# HARE_Main_Sch_Rev1.net
KiCad netlist of a schematic drawn in EAGLE
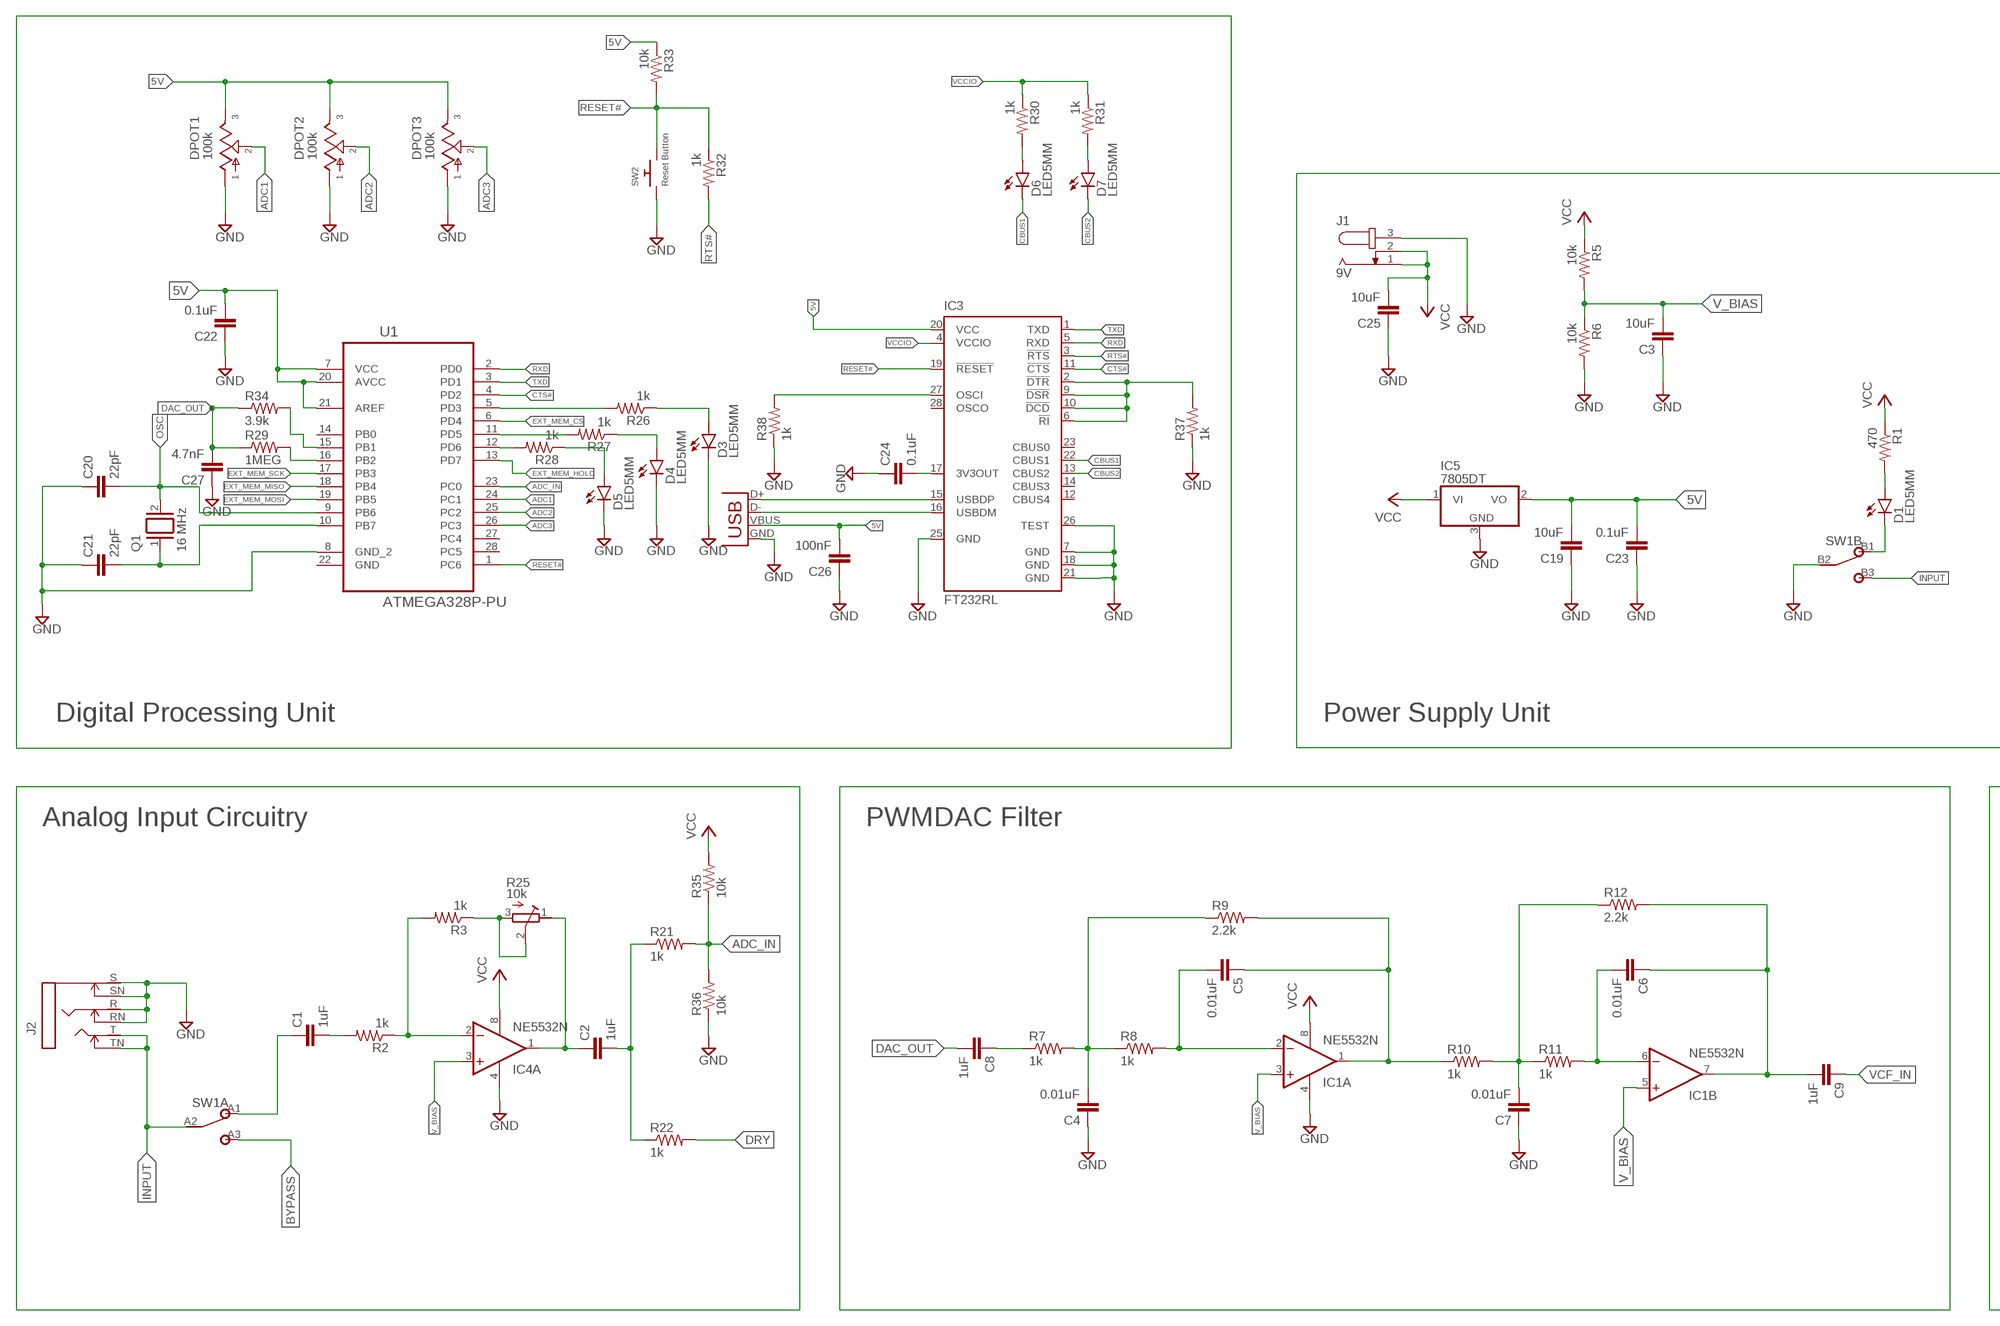
[diagram p0: schematic, sheet 1, part 1 of 2]
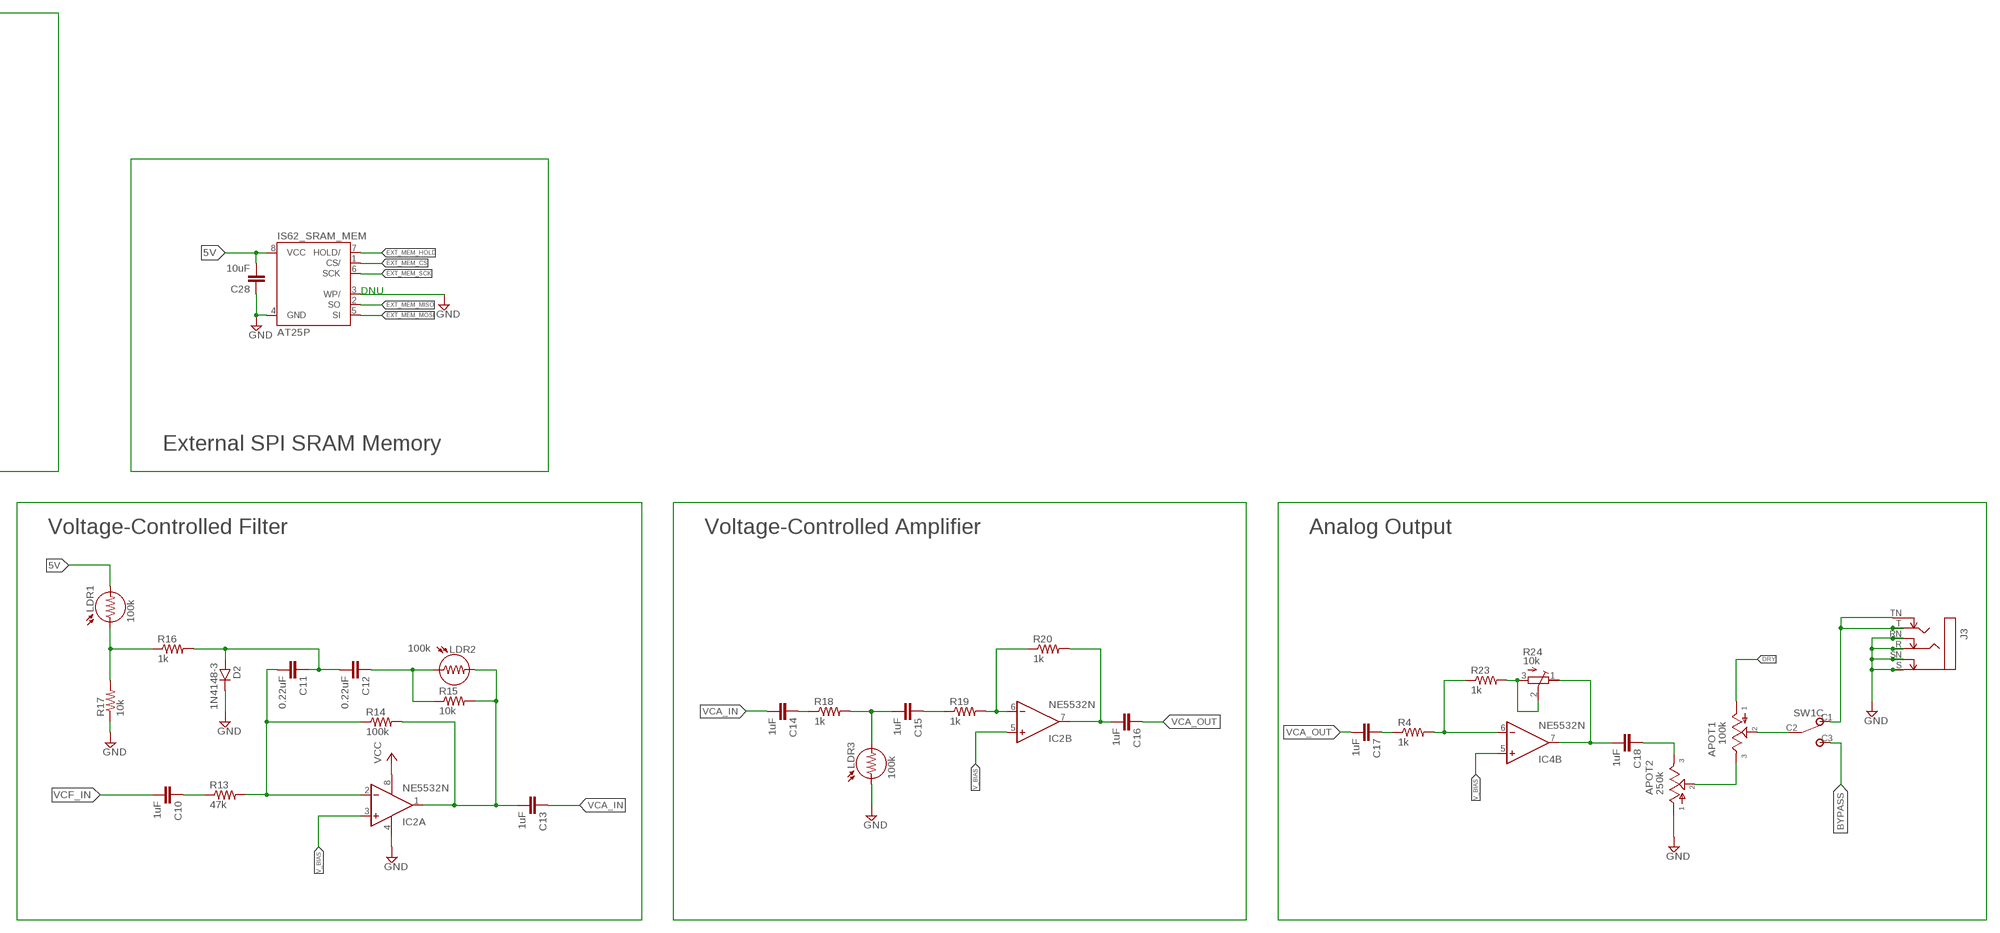
[diagram p1: schematic, sheet 1, part 2 of 2]

(export (version "E")
  (design (tool "Eeschema 10.0.6"))
  (components
    (comp (ref "APOT1")
      (value "100k")
      (footprint "eagle-import:16MM-SQUARE")
      (libsource (lib "eagle-import") (part "POTS"))
    )
    (comp (ref "APOT2")
      (value "250k")
      (footprint "eagle-import:16MM-SQUARE")
      (libsource (lib "eagle-import") (part "POTS"))
    )
    (comp (ref "C1")
      (value "1uF")
      (footprint "eagle-import:C0805K")
      (libsource (lib "eagle-import") (part "C-EUC0805K"))
    )
    (comp (ref "C2")
      (value "1uF")
      (footprint "eagle-import:C0805K")
      (libsource (lib "eagle-import") (part "C-EUC0805K"))
    )
    (comp (ref "C3")
      (value "10uF")
      (footprint "eagle-import:C0805K")
      (libsource (lib "eagle-import") (part "C-EUC0805K"))
    )
    (comp (ref "C4")
      (value "0.01uF")
      (footprint "eagle-import:C0805K")
      (libsource (lib "eagle-import") (part "C-EUC0805K"))
    )
    (comp (ref "C5")
      (value "0.01uF")
      (footprint "eagle-import:C0805K")
      (libsource (lib "eagle-import") (part "C-EUC0805K"))
    )
    (comp (ref "C6")
      (value "0.01uF")
      (footprint "eagle-import:C0805K")
      (libsource (lib "eagle-import") (part "C-EUC0805K"))
    )
    (comp (ref "C7")
      (value "0.01uF")
      (footprint "eagle-import:C0805K")
      (libsource (lib "eagle-import") (part "C-EUC0805K"))
    )
    (comp (ref "C8")
      (value "1uF")
      (footprint "eagle-import:C0805K")
      (libsource (lib "eagle-import") (part "C-EUC0805K"))
    )
    (comp (ref "C9")
      (value "1uF")
      (footprint "eagle-import:C0805K")
      (libsource (lib "eagle-import") (part "C-EUC0805K"))
    )
    (comp (ref "C10")
      (value "1uF")
      (footprint "eagle-import:C0805K")
      (libsource (lib "eagle-import") (part "C-EUC0805K"))
    )
    (comp (ref "C11")
      (value "0.22uF")
      (footprint "eagle-import:C0805K")
      (libsource (lib "eagle-import") (part "C-EUC0805K"))
    )
    (comp (ref "C12")
      (value "0.22uF")
      (footprint "eagle-import:C0805K")
      (libsource (lib "eagle-import") (part "C-EUC0805K"))
    )
    (comp (ref "C13")
      (value "1uF")
      (footprint "eagle-import:C0805K")
      (libsource (lib "eagle-import") (part "C-EUC0805K"))
    )
    (comp (ref "C14")
      (value "1uF")
      (footprint "eagle-import:C0805K")
      (libsource (lib "eagle-import") (part "C-EUC0805K"))
    )
    (comp (ref "C15")
      (value "1uF")
      (footprint "eagle-import:C0805K")
      (libsource (lib "eagle-import") (part "C-EUC0805K"))
    )
    (comp (ref "C16")
      (value "1uF")
      (footprint "eagle-import:C0805K")
      (libsource (lib "eagle-import") (part "C-EUC0805K"))
    )
    (comp (ref "C17")
      (value "1uF")
      (footprint "eagle-import:C0805K")
      (libsource (lib "eagle-import") (part "C-EUC0805K"))
    )
    (comp (ref "C18")
      (value "1uF")
      (footprint "eagle-import:C0805K")
      (libsource (lib "eagle-import") (part "C-EUC0805K"))
    )
    (comp (ref "C19")
      (value "10uF")
      (footprint "eagle-import:C0805K")
      (libsource (lib "eagle-import") (part "C-EUC0805K"))
    )
    (comp (ref "C20")
      (value "22pF")
      (footprint "eagle-import:C0805K")
      (libsource (lib "eagle-import") (part "C-EUC0805K"))
    )
    (comp (ref "C21")
      (value "22pF")
      (footprint "eagle-import:C0805K")
      (libsource (lib "eagle-import") (part "C-EUC0805K"))
    )
    (comp (ref "C22")
      (value "0.1uF")
      (footprint "eagle-import:C0805K")
      (libsource (lib "eagle-import") (part "C-EUC0805K"))
    )
    (comp (ref "C23")
      (value "0.1uF")
      (footprint "eagle-import:C0805K")
      (libsource (lib "eagle-import") (part "C-EUC0805K"))
    )
    (comp (ref "C24")
      (value "0.1uF")
      (footprint "eagle-import:C0805K")
      (libsource (lib "eagle-import") (part "C-EUC0805K"))
    )
    (comp (ref "C25")
      (value "10uF")
      (footprint "eagle-import:C0805K")
      (libsource (lib "eagle-import") (part "C-EUC0805K"))
    )
    (comp (ref "C26")
      (value "100nF")
      (footprint "eagle-import:C0805K")
      (libsource (lib "eagle-import") (part "C-EUC0805K"))
    )
    (comp (ref "C27")
      (value "4.7nF")
      (footprint "eagle-import:C0805K")
      (libsource (lib "eagle-import") (part "C-EUC0805K"))
    )
    (comp (ref "C28")
      (value "10uF")
      (footprint "eagle-import:C0805K")
      (libsource (lib "eagle-import") (part "C-EUC0805K"))
    )
    (comp (ref "D1")
      (value "LED5MM")
      (footprint "eagle-import:LED5MM")
      (libsource (lib "eagle-import") (part "LED5MM"))
    )
    (comp (ref "D2")
      (value "1N4148-3")
      (footprint "eagle-import:DO35-3")
      (libsource (lib "eagle-import") (part "1N4148-3"))
    )
    (comp (ref "D3")
      (value "LED5MM")
      (footprint "eagle-import:LED5MM")
      (libsource (lib "eagle-import") (part "LED5MM"))
    )
    (comp (ref "D4")
      (value "LED5MM")
      (footprint "eagle-import:LED5MM")
      (libsource (lib "eagle-import") (part "LED5MM"))
    )
    (comp (ref "D5")
      (value "LED5MM")
      (footprint "eagle-import:LED5MM")
      (libsource (lib "eagle-import") (part "LED5MM"))
    )
    (comp (ref "D6")
      (value "LED5MM")
      (footprint "eagle-import:LED5MM")
      (libsource (lib "eagle-import") (part "LED5MM"))
    )
    (comp (ref "D7")
      (value "LED5MM")
      (footprint "eagle-import:LED5MM")
      (libsource (lib "eagle-import") (part "LED5MM"))
    )
    (comp (ref "DPOT1")
      (value "100k")
      (footprint "eagle-import:16MM-SQUARE")
      (libsource (lib "eagle-import") (part "POTS"))
    )
    (comp (ref "DPOT2")
      (value "100k")
      (footprint "eagle-import:16MM-SQUARE")
      (libsource (lib "eagle-import") (part "POTS"))
    )
    (comp (ref "DPOT3")
      (value "100k")
      (footprint "eagle-import:16MM-SQUARE")
      (libsource (lib "eagle-import") (part "POTS"))
    )
    (comp (ref "IC1")
      (value "NE5532N")
      (footprint "eagle-import:DIL08")
      (libsource (lib "eagle-import") (part "NE5532N"))
    )
    (comp (ref "IC2")
      (value "NE5532N")
      (footprint "eagle-import:DIL08")
      (libsource (lib "eagle-import") (part "NE5532N"))
    )
    (comp (ref "IC3")
      (value "FT232RL")
      (footprint "eagle-import:SSOP28")
      (libsource (lib "eagle-import") (part "FT232RL"))
    )
    (comp (ref "IC4")
      (value "NE5532N")
      (footprint "eagle-import:DIL08")
      (libsource (lib "eagle-import") (part "NE5532N"))
    )
    (comp (ref "IC5")
      (value "7805DT")
      (footprint "eagle-import:TO252")
      (libsource (lib "eagle-import") (part "78DT05"))
    )
    (comp (ref "IS62_SRAM_MEM")
      (value "AT25P")
      (footprint "eagle-import:DIL08")
      (fields (field (name "MPN") "CAT25040LI-G"))
      (libsource (lib "eagle-import") (part "AT25P"))
    )
    (comp (ref "J1")
      (value "9V")
      (footprint "eagle-import:SPC4078")
      (libsource (lib "eagle-import") (part "JACK-PLUG1"))
    )
    (comp (ref "J2")
      (value "STEREOSW")
      (footprint "eagle-import:NMJ6HCD2")
      (libsource (lib "eagle-import") (part "STEREOSW"))
    )
    (comp (ref "J3")
      (value "STEREOSW")
      (footprint "eagle-import:NMJ6HCD2")
      (libsource (lib "eagle-import") (part "STEREOSW"))
    )
    (comp (ref "LDR1")
      (value "100k")
      (footprint "eagle-import:LDR338-54C")
      (libsource (lib "eagle-import") (part "LDR5MM"))
    )
    (comp (ref "LDR2")
      (value "100k")
      (footprint "eagle-import:LDR338-54C")
      (libsource (lib "eagle-import") (part "LDR5MM"))
    )
    (comp (ref "LDR3")
      (value "100k")
      (footprint "eagle-import:LDR338-54C")
      (libsource (lib "eagle-import") (part "LDR5MM"))
    )
    (comp (ref "Q1")
      (value "16 MHz")
      (footprint "eagle-import:QS")
      (libsource (lib "eagle-import") (part "XTAL/S"))
    )
    (comp (ref "R1")
      (value "470")
      (footprint "eagle-import:M0805")
      (libsource (lib "eagle-import") (part "R-US_M0805"))
    )
    (comp (ref "R2")
      (value "1k")
      (footprint "eagle-import:R0805")
      (libsource (lib "eagle-import") (part "resistor_R-US_R0805"))
    )
    (comp (ref "R3")
      (value "1k")
      (footprint "eagle-import:R0805")
      (libsource (lib "eagle-import") (part "resistor_R-US_R0805"))
    )
    (comp (ref "R4")
      (value "1k")
      (footprint "eagle-import:R0805")
      (libsource (lib "eagle-import") (part "resistor_R-US_R0805"))
    )
    (comp (ref "R5")
      (value "10k")
      (footprint "eagle-import:M0805")
      (libsource (lib "eagle-import") (part "R-US_M0805"))
    )
    (comp (ref "R6")
      (value "10k")
      (footprint "eagle-import:M0805")
      (libsource (lib "eagle-import") (part "R-US_M0805"))
    )
    (comp (ref "R7")
      (value "1k")
      (footprint "eagle-import:R0805")
      (libsource (lib "eagle-import") (part "resistor_R-US_R0805"))
    )
    (comp (ref "R8")
      (value "1k")
      (footprint "eagle-import:R0805")
      (libsource (lib "eagle-import") (part "resistor_R-US_R0805"))
    )
    (comp (ref "R9")
      (value "2.2k")
      (footprint "eagle-import:R0805")
      (libsource (lib "eagle-import") (part "resistor_R-US_R0805"))
    )
    (comp (ref "R10")
      (value "1k")
      (footprint "eagle-import:R0805")
      (libsource (lib "eagle-import") (part "resistor_R-US_R0805"))
    )
    (comp (ref "R11")
      (value "1k")
      (footprint "eagle-import:R0805")
      (libsource (lib "eagle-import") (part "resistor_R-US_R0805"))
    )
    (comp (ref "R12")
      (value "2.2k")
      (footprint "eagle-import:R0805")
      (libsource (lib "eagle-import") (part "resistor_R-US_R0805"))
    )
    (comp (ref "R13")
      (value "47k")
      (footprint "eagle-import:R0805")
      (libsource (lib "eagle-import") (part "resistor_R-US_R0805"))
    )
    (comp (ref "R14")
      (value "100k")
      (footprint "eagle-import:R0805")
      (libsource (lib "eagle-import") (part "resistor_R-US_R0805"))
    )
    (comp (ref "R15")
      (value "10k")
      (footprint "eagle-import:R0805")
      (libsource (lib "eagle-import") (part "resistor_R-US_R0805"))
    )
    (comp (ref "R16")
      (value "1k")
      (footprint "eagle-import:R0805")
      (libsource (lib "eagle-import") (part "resistor_R-US_R0805"))
    )
    (comp (ref "R17")
      (value "10k")
      (footprint "eagle-import:R0805")
      (libsource (lib "eagle-import") (part "resistor_R-US_R0805"))
    )
    (comp (ref "R18")
      (value "1k")
      (footprint "eagle-import:R0805")
      (libsource (lib "eagle-import") (part "resistor_R-US_R0805"))
    )
    (comp (ref "R19")
      (value "1k")
      (footprint "eagle-import:R0805")
      (libsource (lib "eagle-import") (part "resistor_R-US_R0805"))
    )
    (comp (ref "R20")
      (value "1k")
      (footprint "eagle-import:R0805")
      (libsource (lib "eagle-import") (part "resistor_R-US_R0805"))
    )
    (comp (ref "R21")
      (value "1k")
      (footprint "eagle-import:R0805")
      (libsource (lib "eagle-import") (part "resistor_R-US_R0805"))
    )
    (comp (ref "R22")
      (value "1k")
      (footprint "eagle-import:R0805")
      (libsource (lib "eagle-import") (part "resistor_R-US_R0805"))
    )
    (comp (ref "R23")
      (value "1k")
      (footprint "eagle-import:R0805")
      (libsource (lib "eagle-import") (part "resistor_R-US_R0805"))
    )
    (comp (ref "R24")
      (value "10k")
      (footprint "eagle-import:RTRIM3314G")
      (libsource (lib "eagle-import") (part "R-TRIMM3314G"))
    )
    (comp (ref "R25")
      (value "10k")
      (footprint "eagle-import:RTRIM3314G")
      (libsource (lib "eagle-import") (part "R-TRIMM3314G"))
    )
    (comp (ref "R26")
      (value "1k")
      (footprint "eagle-import:R0805")
      (libsource (lib "eagle-import") (part "resistor_R-US_R0805"))
    )
    (comp (ref "R27")
      (value "1k")
      (footprint "eagle-import:R0805")
      (libsource (lib "eagle-import") (part "resistor_R-US_R0805"))
    )
    (comp (ref "R28")
      (value "1k")
      (footprint "eagle-import:R0805")
      (libsource (lib "eagle-import") (part "resistor_R-US_R0805"))
    )
    (comp (ref "R29")
      (value "1MEG")
      (footprint "eagle-import:R0805")
      (libsource (lib "eagle-import") (part "resistor_R-US_R0805"))
    )
    (comp (ref "R30")
      (value "1k")
      (footprint "eagle-import:R0805")
      (libsource (lib "eagle-import") (part "resistor_R-US_R0805"))
    )
    (comp (ref "R31")
      (value "1k")
      (footprint "eagle-import:R0805")
      (libsource (lib "eagle-import") (part "resistor_R-US_R0805"))
    )
    (comp (ref "R32")
      (value "1k")
      (footprint "eagle-import:R0805")
      (libsource (lib "eagle-import") (part "resistor_R-US_R0805"))
    )
    (comp (ref "R33")
      (value "10k")
      (footprint "eagle-import:R0805")
      (libsource (lib "eagle-import") (part "resistor_R-US_R0805"))
    )
    (comp (ref "R34")
      (value "3.9k")
      (footprint "eagle-import:R0805")
      (libsource (lib "eagle-import") (part "resistor_R-US_R0805"))
    )
    (comp (ref "R35")
      (value "10k")
      (footprint "eagle-import:R0805")
      (libsource (lib "eagle-import") (part "resistor_R-US_R0805"))
    )
    (comp (ref "R36")
      (value "10k")
      (footprint "eagle-import:R0805")
      (libsource (lib "eagle-import") (part "resistor_R-US_R0805"))
    )
    (comp (ref "R37")
      (value "1k")
      (footprint "eagle-import:R0805")
      (libsource (lib "eagle-import") (part "resistor_R-US_R0805"))
    )
    (comp (ref "R38")
      (value "1k")
      (footprint "eagle-import:R0805")
      (libsource (lib "eagle-import") (part "resistor_R-US_R0805"))
    )
    (comp (ref "SW1")
      (value "3PDTBLUE")
      (footprint "eagle-import:CHINABLUE")
      (libsource (lib "eagle-import") (part "3PDTBLUE"))
    )
    (comp (ref "SW2")
      (value "Reset Button")
      (footprint "eagle-import:PUSHBUTTON_SMD_SJ")
      (libsource (lib "eagle-import") (part "SWITCH_PUSHBUTTONSOFTTOUCHSMD_SJ"))
    )
    (comp (ref "U1")
      (value "ATMEGA328P-PU")
      (footprint "eagle-import:DIP254P762X457-28")
      (libsource (lib "eagle-import") (part "ATMEGA328P-PU"))
    )
    (comp (ref "X2")
      (value "USB-B-H")
      (footprint "eagle-import:USB-B-H")
      (libsource (lib "eagle-import") (part "USB-B-H"))
    )
  )
  (nets
    (net (code "1") (name "5V") (class "Default")
      (node (ref "C19") (pin "2") (pinfunction "2_2") (pintype "passive"))
      (node (ref "C22") (pin "2") (pinfunction "2_2") (pintype "passive"))
      (node (ref "C23") (pin "2") (pinfunction "2_2") (pintype "passive"))
      (node (ref "C26") (pin "2") (pinfunction "2_2") (pintype "passive"))
      (node (ref "C28") (pin "2") (pinfunction "2_2") (pintype "passive"))
      (node (ref "DPOT1") (pin "3") (pinfunction "3_3") (pintype "passive"))
      (node (ref "DPOT2") (pin "3") (pinfunction "3_3") (pintype "passive"))
      (node (ref "DPOT3") (pin "3") (pinfunction "3_3") (pintype "passive"))
      (node (ref "IC3") (pin "20") (pinfunction "VCC_20") (pintype "power_in"))
      (node (ref "IC5") (pin "2") (pinfunction "VO_2") (pintype "passive"))
      (node (ref "IS62_SRAM_MEM") (pin "8") (pinfunction "VCC_8") (pintype "power_in"))
      (node (ref "LDR1") (pin "2") (pinfunction "2_2") (pintype "passive"))
      (node (ref "R33") (pin "1") (pinfunction "1_1") (pintype "passive"))
      (node (ref "U1") (pin "20") (pinfunction "AVCC_20") (pintype "power_in"))
      (node (ref "U1") (pin "21") (pinfunction "AREF_21") (pintype "input"))
      (node (ref "U1") (pin "7") (pinfunction "VCC_7") (pintype "power_in"))
      (node (ref "X2") (pin "VBUS") (pinfunction "VBUS_VBUS") (pintype "bidirectional"))
    )
    (net (code "2") (name "ADC1") (class "Default")
      (node (ref "DPOT1") (pin "2") (pinfunction "2_2") (pintype "passive"))
      (node (ref "U1") (pin "24") (pinfunction "PC1_24") (pintype "bidirectional"))
    )
    (net (code "3") (name "ADC2") (class "Default")
      (node (ref "DPOT2") (pin "2") (pinfunction "2_2") (pintype "passive"))
      (node (ref "U1") (pin "25") (pinfunction "PC2_25") (pintype "bidirectional"))
    )
    (net (code "4") (name "ADC3") (class "Default")
      (node (ref "DPOT3") (pin "2") (pinfunction "2_2") (pintype "passive"))
      (node (ref "U1") (pin "26") (pinfunction "PC3_26") (pintype "bidirectional"))
    )
    (net (code "5") (name "ADC_IN") (class "Default")
      (node (ref "R21") (pin "2") (pinfunction "2_2") (pintype "passive"))
      (node (ref "R35") (pin "1") (pinfunction "1_1") (pintype "passive"))
      (node (ref "R36") (pin "2") (pinfunction "2_2") (pintype "passive"))
      (node (ref "U1") (pin "23") (pinfunction "PC0_23") (pintype "bidirectional"))
    )
    (net (code "6") (name "BYPASS") (class "Default")
      (node (ref "SW1") (pin "A3") (pinfunction "3_A3") (pintype "passive"))
      (node (ref "SW1") (pin "C3") (pinfunction "3_C3") (pintype "passive"))
    )
    (net (code "7") (name "CBUS1") (class "Default")
      (node (ref "D6") (pin "K") (pinfunction "C_K") (pintype "passive"))
      (node (ref "IC3") (pin "22") (pinfunction "CBUS1_22") (pintype "bidirectional"))
    )
    (net (code "8") (name "CBUS2") (class "Default")
      (node (ref "D7") (pin "K") (pinfunction "C_K") (pintype "passive"))
      (node (ref "IC3") (pin "13") (pinfunction "CBUS2_13") (pintype "bidirectional"))
    )
    (net (code "9") (name "CTS#") (class "Default")
      (node (ref "IC3") (pin "11") (pinfunction "~{CTS}_11") (pintype "input"))
      (node (ref "U1") (pin "4") (pinfunction "PD2_4") (pintype "bidirectional"))
    )
    (net (code "10") (name "DAC_OUT") (class "Default")
      (node (ref "C27") (pin "2") (pinfunction "2_2") (pintype "passive"))
      (node (ref "C8") (pin "2") (pinfunction "2_2") (pintype "passive"))
      (node (ref "R29") (pin "1") (pinfunction "1_1") (pintype "passive"))
      (node (ref "R34") (pin "1") (pinfunction "1_1") (pintype "passive"))
    )
    (net (code "11") (name "DRY") (class "Default")
      (node (ref "APOT1") (pin "1") (pinfunction "1_1") (pintype "passive"))
      (node (ref "R22") (pin "2") (pinfunction "2_2") (pintype "passive"))
    )
    (net (code "12") (name "EXT_MEM_CS") (class "Default")
      (node (ref "IS62_SRAM_MEM") (pin "1") (pinfunction "CS/_1") (pintype "input"))
      (node (ref "U1") (pin "6") (pinfunction "PD4_6") (pintype "bidirectional"))
    )
    (net (code "13") (name "EXT_MEM_HOLD") (class "Default")
      (node (ref "IS62_SRAM_MEM") (pin "7") (pinfunction "HOLD/_7") (pintype "input"))
      (node (ref "U1") (pin "13") (pinfunction "PD7_13") (pintype "bidirectional"))
    )
    (net (code "14") (name "EXT_MEM_MISO") (class "Default")
      (node (ref "IS62_SRAM_MEM") (pin "2") (pinfunction "SO_2") (pintype "input"))
      (node (ref "U1") (pin "18") (pinfunction "PB4_18") (pintype "bidirectional"))
    )
    (net (code "15") (name "EXT_MEM_MOSI") (class "Default")
      (node (ref "IS62_SRAM_MEM") (pin "5") (pinfunction "SI_5") (pintype "bidirectional"))
      (node (ref "U1") (pin "19") (pinfunction "PB5_19") (pintype "bidirectional"))
    )
    (net (code "16") (name "EXT_MEM_SCK") (class "Default")
      (node (ref "IS62_SRAM_MEM") (pin "6") (pinfunction "SCK_6") (pintype "bidirectional"))
      (node (ref "U1") (pin "17") (pinfunction "PB3_17") (pintype "bidirectional"))
    )
    (net (code "17") (name "GND") (class "Default")
      (node (ref "APOT2") (pin "1") (pinfunction "1_1") (pintype "passive"))
      (node (ref "C19") (pin "1") (pinfunction "1_1") (pintype "passive"))
      (node (ref "C20") (pin "1") (pinfunction "1_1") (pintype "passive"))
      (node (ref "C21") (pin "1") (pinfunction "1_1") (pintype "passive"))
      (node (ref "C22") (pin "1") (pinfunction "1_1") (pintype "passive"))
      (node (ref "C23") (pin "1") (pinfunction "1_1") (pintype "passive"))
      (node (ref "C24") (pin "1") (pinfunction "1_1") (pintype "passive"))
      (node (ref "C25") (pin "1") (pinfunction "1_1") (pintype "passive"))
      (node (ref "C26") (pin "1") (pinfunction "1_1") (pintype "passive"))
      (node (ref "C27") (pin "1") (pinfunction "1_1") (pintype "passive"))
      (node (ref "C28") (pin "1") (pinfunction "1_1") (pintype "passive"))
      (node (ref "C3") (pin "1") (pinfunction "1_1") (pintype "passive"))
      (node (ref "C4") (pin "1") (pinfunction "1_1") (pintype "passive"))
      (node (ref "C7") (pin "1") (pinfunction "1_1") (pintype "passive"))
      (node (ref "D2") (pin "C") (pinfunction "C_C") (pintype "passive"))
      (node (ref "D3") (pin "K") (pinfunction "C_K") (pintype "passive"))
      (node (ref "D4") (pin "K") (pinfunction "C_K") (pintype "passive"))
      (node (ref "D5") (pin "K") (pinfunction "C_K") (pintype "passive"))
      (node (ref "DPOT1") (pin "1") (pinfunction "1_1") (pintype "passive"))
      (node (ref "DPOT2") (pin "1") (pinfunction "1_1") (pintype "passive"))
      (node (ref "DPOT3") (pin "1") (pinfunction "1_1") (pintype "passive"))
      (node (ref "IC1") (pin "4") (pinfunction "V-_4") (pintype "power_in"))
      (node (ref "IC2") (pin "4") (pinfunction "V-_4") (pintype "power_in"))
      (node (ref "IC3") (pin "18") (pinfunction "GND_18") (pintype "power_in"))
      (node (ref "IC3") (pin "21") (pinfunction "GND_21") (pintype "power_in"))
      (node (ref "IC3") (pin "25") (pinfunction "GND_25") (pintype "power_in"))
      (node (ref "IC3") (pin "26") (pinfunction "TEST_26") (pintype "input"))
      (node (ref "IC3") (pin "7") (pinfunction "GND_7") (pintype "power_in"))
      (node (ref "IC4") (pin "4") (pinfunction "V-_4") (pintype "power_in"))
      (node (ref "IC5") (pin "3") (pinfunction "GND_3") (pintype "passive"))
      (node (ref "IS62_SRAM_MEM") (pin "3") (pinfunction "WP/_3") (pintype "input"))
      (node (ref "IS62_SRAM_MEM") (pin "4") (pinfunction "GND_4") (pintype "power_in"))
      (node (ref "J1") (pin "3") (pinfunction "3_3") (pintype "passive"))
      (node (ref "J2") (pin "R") (pinfunction "R_R") (pintype "passive"))
      (node (ref "J2") (pin "RN") (pinfunction "RN_RN") (pintype "passive"))
      (node (ref "J2") (pin "S") (pinfunction "S_S") (pintype "passive"))
      (node (ref "J2") (pin "SN") (pinfunction "SN_SN") (pintype "passive"))
      (node (ref "J3") (pin "R") (pinfunction "R_R") (pintype "passive"))
      (node (ref "J3") (pin "RN") (pinfunction "RN_RN") (pintype "passive"))
      (node (ref "J3") (pin "S") (pinfunction "S_S") (pintype "passive"))
      (node (ref "J3") (pin "SN") (pinfunction "SN_SN") (pintype "passive"))
      (node (ref "LDR3") (pin "1") (pinfunction "1_1") (pintype "passive"))
      (node (ref "R17") (pin "1") (pinfunction "1_1") (pintype "passive"))
      (node (ref "R36") (pin "1") (pinfunction "1_1") (pintype "passive"))
      (node (ref "R37") (pin "1") (pinfunction "1_1") (pintype "passive"))
      (node (ref "R38") (pin "1") (pinfunction "1_1") (pintype "passive"))
      (node (ref "R6") (pin "2") (pinfunction "2_2") (pintype "passive"))
      (node (ref "SW1") (pin "B2") (pinfunction "2_B2") (pintype "passive"))
      (node (ref "SW2") (pin "P$1") (pinfunction "P$1_P$1") (pintype "passive"))
      (node (ref "U1") (pin "8") (pinfunction "GND_2_8") (pintype "passive"))
      (node (ref "X2") (pin "GND") (pinfunction "GND_GND") (pintype "bidirectional"))
    )
    (net (code "18") (name "INPUT") (class "Default")
      (node (ref "J2") (pin "T") (pinfunction "T_T") (pintype "passive"))
      (node (ref "J2") (pin "TN") (pinfunction "TN_TN") (pintype "passive"))
      (node (ref "SW1") (pin "A2") (pinfunction "2_A2") (pintype "passive"))
      (node (ref "SW1") (pin "B3") (pinfunction "3_B3") (pintype "passive"))
    )
    (net (code "19") (name "Net-(APOT1-Pad3)") (class "Default")
      (node (ref "APOT1") (pin "3") (pinfunction "3_3") (pintype "passive"))
      (node (ref "APOT2") (pin "2") (pinfunction "2_2") (pintype "passive"))
    )
    (net (code "20") (name "Net-(APOT2-Pad3)") (class "Default")
      (node (ref "APOT2") (pin "3") (pinfunction "3_3") (pintype "passive"))
      (node (ref "C18") (pin "1") (pinfunction "1_1") (pintype "passive"))
    )
    (net (code "21") (name "Net-(C1-Pad2)") (class "Default")
      (node (ref "C1") (pin "2") (pinfunction "2_2") (pintype "passive"))
      (node (ref "R2") (pin "2") (pinfunction "2_2") (pintype "passive"))
    )
    (net (code "22") (name "Net-(C2-Pad2)") (class "Default")
      (node (ref "C2") (pin "2") (pinfunction "2_2") (pintype "passive"))
      (node (ref "R21") (pin "1") (pinfunction "1_1") (pintype "passive"))
      (node (ref "R22") (pin "1") (pinfunction "1_1") (pintype "passive"))
    )
    (net (code "23") (name "Net-(C4-Pad2)") (class "Default")
      (node (ref "C4") (pin "2") (pinfunction "2_2") (pintype "passive"))
      (node (ref "R7") (pin "2") (pinfunction "2_2") (pintype "passive"))
      (node (ref "R8") (pin "1") (pinfunction "1_1") (pintype "passive"))
      (node (ref "R9") (pin "1") (pinfunction "1_1") (pintype "passive"))
    )
    (net (code "24") (name "Net-(C7-Pad2)") (class "Default")
      (node (ref "C7") (pin "2") (pinfunction "2_2") (pintype "passive"))
      (node (ref "R10") (pin "2") (pinfunction "2_2") (pintype "passive"))
      (node (ref "R11") (pin "1") (pinfunction "1_1") (pintype "passive"))
      (node (ref "R12") (pin "1") (pinfunction "1_1") (pintype "passive"))
    )
    (net (code "25") (name "Net-(C8-Pad1)") (class "Default")
      (node (ref "C8") (pin "1") (pinfunction "1_1") (pintype "passive"))
      (node (ref "R7") (pin "1") (pinfunction "1_1") (pintype "passive"))
    )
    (net (code "26") (name "Net-(C10-Pad1)") (class "Default")
      (node (ref "C10") (pin "1") (pinfunction "1_1") (pintype "passive"))
      (node (ref "R13") (pin "1") (pinfunction "1_1") (pintype "passive"))
    )
    (net (code "27") (name "Net-(C11-Pad1)") (class "Default")
      (node (ref "C11") (pin "1") (pinfunction "1_1") (pintype "passive"))
      (node (ref "C12") (pin "2") (pinfunction "2_2") (pintype "passive"))
      (node (ref "D2") (pin "A") (pinfunction "A_A") (pintype "passive"))
      (node (ref "R16") (pin "2") (pinfunction "2_2") (pintype "passive"))
    )
    (net (code "28") (name "Net-(C12-Pad1)") (class "Default")
      (node (ref "C12") (pin "1") (pinfunction "1_1") (pintype "passive"))
      (node (ref "LDR2") (pin "1") (pinfunction "1_1") (pintype "passive"))
      (node (ref "R15") (pin "1") (pinfunction "1_1") (pintype "passive"))
    )
    (net (code "29") (name "Net-(C14-Pad1)") (class "Default")
      (node (ref "C14") (pin "1") (pinfunction "1_1") (pintype "passive"))
      (node (ref "R18") (pin "1") (pinfunction "1_1") (pintype "passive"))
    )
    (net (code "30") (name "Net-(C15-Pad1)") (class "Default")
      (node (ref "C15") (pin "1") (pinfunction "1_1") (pintype "passive"))
      (node (ref "R19") (pin "1") (pinfunction "1_1") (pintype "passive"))
    )
    (net (code "31") (name "Net-(C15-Pad2)") (class "Default")
      (node (ref "C15") (pin "2") (pinfunction "2_2") (pintype "passive"))
      (node (ref "LDR3") (pin "2") (pinfunction "2_2") (pintype "passive"))
      (node (ref "R18") (pin "2") (pinfunction "2_2") (pintype "passive"))
    )
    (net (code "32") (name "Net-(C17-Pad1)") (class "Default")
      (node (ref "C17") (pin "1") (pinfunction "1_1") (pintype "passive"))
      (node (ref "R4") (pin "1") (pinfunction "1_1") (pintype "passive"))
    )
    (net (code "33") (name "Net-(D1-C)") (class "Default")
      (node (ref "D1") (pin "K") (pinfunction "C_K") (pintype "passive"))
      (node (ref "SW1") (pin "B1") (pinfunction "1_B1") (pintype "passive"))
    )
    (net (code "34") (name "Net-(D1-PadA)") (class "Default")
      (node (ref "D1") (pin "A") (pinfunction "A_A") (pintype "passive"))
      (node (ref "R1") (pin "2") (pinfunction "2_2") (pintype "passive"))
    )
    (net (code "35") (name "Net-(D3-PadA)") (class "Default")
      (node (ref "D3") (pin "A") (pinfunction "A_A") (pintype "passive"))
      (node (ref "R26") (pin "1") (pinfunction "1_1") (pintype "passive"))
    )
    (net (code "36") (name "Net-(D4-PadA)") (class "Default")
      (node (ref "D4") (pin "A") (pinfunction "A_A") (pintype "passive"))
      (node (ref "R27") (pin "1") (pinfunction "1_1") (pintype "passive"))
    )
    (net (code "37") (name "Net-(D5-PadA)") (class "Default")
      (node (ref "D5") (pin "A") (pinfunction "A_A") (pintype "passive"))
      (node (ref "R28") (pin "1") (pinfunction "1_1") (pintype "passive"))
    )
    (net (code "38") (name "Net-(D6-PadA)") (class "Default")
      (node (ref "D6") (pin "A") (pinfunction "A_A") (pintype "passive"))
      (node (ref "R30") (pin "2") (pinfunction "2_2") (pintype "passive"))
    )
    (net (code "39") (name "Net-(D7-PadA)") (class "Default")
      (node (ref "D7") (pin "A") (pinfunction "A_A") (pintype "passive"))
      (node (ref "R31") (pin "2") (pinfunction "2_2") (pintype "passive"))
    )
    (net (code "40") (name "Net-(IC1A--IN)") (class "Default")
      (node (ref "C5") (pin "2") (pinfunction "2_2") (pintype "passive"))
      (node (ref "IC1") (pin "2") (pinfunction "-IN_2") (pintype "input"))
      (node (ref "R8") (pin "2") (pinfunction "2_2") (pintype "passive"))
    )
    (net (code "41") (name "Net-(IC1A-OUT)") (class "Default")
      (node (ref "C5") (pin "1") (pinfunction "1_1") (pintype "passive"))
      (node (ref "IC1") (pin "1") (pinfunction "OUT_1") (pintype "output"))
      (node (ref "R10") (pin "1") (pinfunction "1_1") (pintype "passive"))
      (node (ref "R9") (pin "2") (pinfunction "2_2") (pintype "passive"))
    )
    (net (code "42") (name "Net-(IC1B--IN)") (class "Default")
      (node (ref "C6") (pin "2") (pinfunction "2_2") (pintype "passive"))
      (node (ref "IC1") (pin "6") (pinfunction "-IN_6") (pintype "input"))
      (node (ref "R11") (pin "2") (pinfunction "2_2") (pintype "passive"))
    )
    (net (code "43") (name "Net-(IC1B-OUT)") (class "Default")
      (node (ref "C6") (pin "1") (pinfunction "1_1") (pintype "passive"))
      (node (ref "C9") (pin "2") (pinfunction "2_2") (pintype "passive"))
      (node (ref "IC1") (pin "7") (pinfunction "OUT_7") (pintype "output"))
      (node (ref "R12") (pin "2") (pinfunction "2_2") (pintype "passive"))
    )
    (net (code "44") (name "Net-(IC2A--IN)") (class "Default")
      (node (ref "C11") (pin "2") (pinfunction "2_2") (pintype "passive"))
      (node (ref "IC2") (pin "2") (pinfunction "-IN_2") (pintype "input"))
      (node (ref "R13") (pin "2") (pinfunction "2_2") (pintype "passive"))
      (node (ref "R14") (pin "1") (pinfunction "1_1") (pintype "passive"))
    )
    (net (code "45") (name "Net-(IC2A-OUT)") (class "Default")
      (node (ref "C13") (pin "2") (pinfunction "2_2") (pintype "passive"))
      (node (ref "IC2") (pin "1") (pinfunction "OUT_1") (pintype "output"))
      (node (ref "LDR2") (pin "2") (pinfunction "2_2") (pintype "passive"))
      (node (ref "R14") (pin "2") (pinfunction "2_2") (pintype "passive"))
      (node (ref "R15") (pin "2") (pinfunction "2_2") (pintype "passive"))
    )
    (net (code "46") (name "Net-(IC2B--IN)") (class "Default")
      (node (ref "IC2") (pin "6") (pinfunction "-IN_6") (pintype "input"))
      (node (ref "R19") (pin "2") (pinfunction "2_2") (pintype "passive"))
      (node (ref "R20") (pin "1") (pinfunction "1_1") (pintype "passive"))
    )
    (net (code "47") (name "Net-(IC2B-OUT)") (class "Default")
      (node (ref "C16") (pin "2") (pinfunction "2_2") (pintype "passive"))
      (node (ref "IC2") (pin "7") (pinfunction "OUT_7") (pintype "output"))
      (node (ref "R20") (pin "2") (pinfunction "2_2") (pintype "passive"))
    )
    (net (code "48") (name "Net-(IC3-3V3OUT)") (class "Default")
      (node (ref "C24") (pin "2") (pinfunction "2_2") (pintype "passive"))
      (node (ref "IC3") (pin "17") (pinfunction "3V3OUT_17") (pintype "output"))
    )
    (net (code "49") (name "Net-(IC3-OSCI)") (class "Default")
      (node (ref "IC3") (pin "27") (pinfunction "OSCI_27") (pintype "input"))
      (node (ref "R38") (pin "2") (pinfunction "2_2") (pintype "passive"))
    )
    (net (code "50") (name "Net-(IC3-USBDM)") (class "Default")
      (node (ref "IC3") (pin "16") (pinfunction "USBDM_16") (pintype "bidirectional"))
      (node (ref "X2") (pin "D-") (pinfunction "D-_D-") (pintype "bidirectional"))
    )
    (net (code "51") (name "Net-(IC3-USBDP)") (class "Default")
      (node (ref "IC3") (pin "15") (pinfunction "USBDP_15") (pintype "bidirectional"))
      (node (ref "X2") (pin "D+") (pinfunction "D+_D+") (pintype "bidirectional"))
    )
    (net (code "52") (name "Net-(IC3-~{DCD})") (class "Default")
      (node (ref "IC3") (pin "10") (pinfunction "~{DCD}_10") (pintype "input"))
      (node (ref "IC3") (pin "2") (pinfunction "~{DTR}_2") (pintype "output"))
      (node (ref "IC3") (pin "6") (pinfunction "~{RI}_6") (pintype "input"))
      (node (ref "IC3") (pin "9") (pinfunction "~{DSR}_9") (pintype "input"))
      (node (ref "R37") (pin "2") (pinfunction "2_2") (pintype "passive"))
    )
    (net (code "53") (name "Net-(IC4A--IN)") (class "Default")
      (node (ref "IC4") (pin "2") (pinfunction "-IN_2") (pintype "input"))
      (node (ref "R2") (pin "1") (pinfunction "1_1") (pintype "passive"))
      (node (ref "R3") (pin "2") (pinfunction "2_2") (pintype "passive"))
    )
    (net (code "54") (name "Net-(IC4A-OUT)") (class "Default")
      (node (ref "C2") (pin "1") (pinfunction "1_1") (pintype "passive"))
      (node (ref "IC4") (pin "1") (pinfunction "OUT_1") (pintype "output"))
      (node (ref "R25") (pin "1") (pinfunction "E_1") (pintype "passive"))
    )
    (net (code "55") (name "Net-(IC4B--IN)") (class "Default")
      (node (ref "IC4") (pin "6") (pinfunction "-IN_6") (pintype "input"))
      (node (ref "R23") (pin "1") (pinfunction "1_1") (pintype "passive"))
      (node (ref "R4") (pin "2") (pinfunction "2_2") (pintype "passive"))
    )
    (net (code "56") (name "Net-(IC4B-OUT)") (class "Default")
      (node (ref "C18") (pin "2") (pinfunction "2_2") (pintype "passive"))
      (node (ref "IC4") (pin "7") (pinfunction "OUT_7") (pintype "output"))
      (node (ref "R24") (pin "1") (pinfunction "E_1") (pintype "passive"))
    )
    (net (code "57") (name "Net-(LDR1-Pad1)") (class "Default")
      (node (ref "LDR1") (pin "1") (pinfunction "1_1") (pintype "passive"))
      (node (ref "R16") (pin "1") (pinfunction "1_1") (pintype "passive"))
      (node (ref "R17") (pin "2") (pinfunction "2_2") (pintype "passive"))
    )
    (net (code "58") (name "Net-(R24-A)") (class "Default")
      (node (ref "R23") (pin "2") (pinfunction "2_2") (pintype "passive"))
      (node (ref "R24") (pin "2") (pinfunction "S_2") (pintype "passive"))
      (node (ref "R24") (pin "3") (pinfunction "A_3") (pintype "passive"))
    )
    (net (code "59") (name "Net-(R25-A)") (class "Default")
      (node (ref "R25") (pin "2") (pinfunction "S_2") (pintype "passive"))
      (node (ref "R25") (pin "3") (pinfunction "A_3") (pintype "passive"))
      (node (ref "R3") (pin "1") (pinfunction "1_1") (pintype "passive"))
    )
    (net (code "60") (name "Net-(SW1A-1)") (class "Default")
      (node (ref "C1") (pin "1") (pinfunction "1_1") (pintype "passive"))
      (node (ref "SW1") (pin "A1") (pinfunction "1_A1") (pintype "passive"))
    )
    (net (code "61") (name "Net-(SW1C-1)") (class "Default")
      (node (ref "J3") (pin "T") (pinfunction "T_T") (pintype "passive"))
      (node (ref "J3") (pin "TN") (pinfunction "TN_TN") (pintype "passive"))
      (node (ref "SW1") (pin "C1") (pinfunction "1_C1") (pintype "passive"))
    )
    (net (code "62") (name "Net-(SW1C-2)") (class "Default")
      (node (ref "APOT1") (pin "2") (pinfunction "2_2") (pintype "passive"))
      (node (ref "SW1") (pin "C2") (pinfunction "2_C2") (pintype "passive"))
    )
    (net (code "63") (name "Net-(U1-PB1)") (class "Default")
      (node (ref "R34") (pin "2") (pinfunction "2_2") (pintype "passive"))
      (node (ref "U1") (pin "15") (pinfunction "PB1_15") (pintype "bidirectional"))
    )
    (net (code "64") (name "Net-(U1-PB2)") (class "Default")
      (node (ref "R29") (pin "2") (pinfunction "2_2") (pintype "passive"))
      (node (ref "U1") (pin "16") (pinfunction "PB2_16") (pintype "bidirectional"))
    )
    (net (code "65") (name "Net-(U1-PB7)") (class "Default")
      (node (ref "C21") (pin "2") (pinfunction "2_2") (pintype "passive"))
      (node (ref "Q1") (pin "1") (pinfunction "1_1") (pintype "passive"))
      (node (ref "U1") (pin "10") (pinfunction "PB7_10") (pintype "bidirectional"))
    )
    (net (code "66") (name "Net-(U1-PD3)") (class "Default")
      (node (ref "R26") (pin "2") (pinfunction "2_2") (pintype "passive"))
      (node (ref "U1") (pin "5") (pinfunction "PD3_5") (pintype "bidirectional"))
    )
    (net (code "67") (name "Net-(U1-PD5)") (class "Default")
      (node (ref "R27") (pin "2") (pinfunction "2_2") (pintype "passive"))
      (node (ref "U1") (pin "11") (pinfunction "PD5_11") (pintype "bidirectional"))
    )
    (net (code "68") (name "Net-(U1-PD6)") (class "Default")
      (node (ref "R28") (pin "2") (pinfunction "2_2") (pintype "passive"))
      (node (ref "U1") (pin "12") (pinfunction "PD6_12") (pintype "bidirectional"))
    )
    (net (code "69") (name "OSC") (class "Default")
      (node (ref "C20") (pin "2") (pinfunction "2_2") (pintype "passive"))
      (node (ref "Q1") (pin "2") (pinfunction "2_2") (pintype "passive"))
      (node (ref "U1") (pin "9") (pinfunction "PB6_9") (pintype "bidirectional"))
    )
    (net (code "70") (name "RESET#") (class "Default")
      (node (ref "IC3") (pin "19") (pinfunction "~{RESET}_19") (pintype "input"))
      (node (ref "R32") (pin "1") (pinfunction "1_1") (pintype "passive"))
      (node (ref "R33") (pin "2") (pinfunction "2_2") (pintype "passive"))
      (node (ref "SW2") (pin "P$2") (pinfunction "P$2_P$2") (pintype "passive"))
      (node (ref "U1") (pin "1") (pinfunction "PC6_1") (pintype "bidirectional"))
    )
    (net (code "71") (name "RTS#") (class "Default")
      (node (ref "IC3") (pin "3") (pinfunction "~{RTS}_3") (pintype "output"))
      (node (ref "R32") (pin "2") (pinfunction "2_2") (pintype "passive"))
    )
    (net (code "72") (name "RXD") (class "Default")
      (node (ref "IC3") (pin "5") (pinfunction "RXD_5") (pintype "input"))
      (node (ref "U1") (pin "2") (pinfunction "PD0_2") (pintype "bidirectional"))
    )
    (net (code "73") (name "TXD") (class "Default")
      (node (ref "IC3") (pin "1") (pinfunction "TXD_1") (pintype "output"))
      (node (ref "U1") (pin "3") (pinfunction "PD1_3") (pintype "bidirectional"))
    )
    (net (code "74") (name "VCA_IN") (class "Default")
      (node (ref "C13") (pin "1") (pinfunction "1_1") (pintype "passive"))
      (node (ref "C14") (pin "2") (pinfunction "2_2") (pintype "passive"))
    )
    (net (code "75") (name "VCA_OUT") (class "Default")
      (node (ref "C16") (pin "1") (pinfunction "1_1") (pintype "passive"))
      (node (ref "C17") (pin "2") (pinfunction "2_2") (pintype "passive"))
    )
    (net (code "76") (name "VCC") (class "Default")
      (node (ref "C25") (pin "2") (pinfunction "2_2") (pintype "passive"))
      (node (ref "IC1") (pin "8") (pinfunction "V+_8") (pintype "power_in"))
      (node (ref "IC2") (pin "8") (pinfunction "V+_8") (pintype "power_in"))
      (node (ref "IC4") (pin "8") (pinfunction "V+_8") (pintype "power_in"))
      (node (ref "IC5") (pin "1") (pinfunction "VI_1") (pintype "input"))
      (node (ref "J1") (pin "1") (pinfunction "1_1") (pintype "passive"))
      (node (ref "J1") (pin "2") (pinfunction "2_2") (pintype "passive"))
      (node (ref "R1") (pin "1") (pinfunction "1_1") (pintype "passive"))
      (node (ref "R35") (pin "2") (pinfunction "2_2") (pintype "passive"))
      (node (ref "R5") (pin "1") (pinfunction "1_1") (pintype "passive"))
    )
    (net (code "77") (name "VCCIO") (class "Default")
      (node (ref "IC3") (pin "4") (pinfunction "VCCIO_4") (pintype "power_in"))
      (node (ref "R30") (pin "1") (pinfunction "1_1") (pintype "passive"))
      (node (ref "R31") (pin "1") (pinfunction "1_1") (pintype "passive"))
    )
    (net (code "78") (name "VCF_IN") (class "Default")
      (node (ref "C10") (pin "2") (pinfunction "2_2") (pintype "passive"))
      (node (ref "C9") (pin "1") (pinfunction "1_1") (pintype "passive"))
    )
    (net (code "79") (name "V_BIAS") (class "Default")
      (node (ref "C3") (pin "2") (pinfunction "2_2") (pintype "passive"))
      (node (ref "IC1") (pin "3") (pinfunction "+IN_3") (pintype "input"))
      (node (ref "IC1") (pin "5") (pinfunction "+IN_5") (pintype "input"))
      (node (ref "IC2") (pin "3") (pinfunction "+IN_3") (pintype "input"))
      (node (ref "IC2") (pin "5") (pinfunction "+IN_5") (pintype "input"))
      (node (ref "IC4") (pin "3") (pinfunction "+IN_3") (pintype "input"))
      (node (ref "IC4") (pin "5") (pinfunction "+IN_5") (pintype "input"))
      (node (ref "R5") (pin "2") (pinfunction "2_2") (pintype "passive"))
      (node (ref "R6") (pin "1") (pinfunction "1_1") (pintype "passive"))
    )
    (net (code "80") (name "unconnected-(IC3-CBUS0-Pad23)") (class "Default")
      (node (ref "IC3") (pin "23") (pinfunction "CBUS0_23") (pintype "bidirectional"))
    )
    (net (code "81") (name "unconnected-(IC3-CBUS3-Pad14)") (class "Default")
      (node (ref "IC3") (pin "14") (pinfunction "CBUS3_14") (pintype "bidirectional"))
    )
    (net (code "82") (name "unconnected-(IC3-CBUS4-Pad12)") (class "Default")
      (node (ref "IC3") (pin "12") (pinfunction "CBUS4_12") (pintype "bidirectional"))
    )
    (net (code "83") (name "unconnected-(IC3-OSCO-Pad28)") (class "Default")
      (node (ref "IC3") (pin "28") (pinfunction "OSCO_28") (pintype "output"))
    )
    (net (code "84") (name "unconnected-(U1-GND-Pad22)") (class "Default")
      (node (ref "U1") (pin "22") (pinfunction "GND_22") (pintype "passive"))
    )
    (net (code "85") (name "unconnected-(U1-PB0-Pad14)") (class "Default")
      (node (ref "U1") (pin "14") (pinfunction "PB0_14") (pintype "bidirectional"))
    )
    (net (code "86") (name "unconnected-(U1-PC4-Pad27)") (class "Default")
      (node (ref "U1") (pin "27") (pinfunction "PC4_27") (pintype "bidirectional"))
    )
    (net (code "87") (name "unconnected-(U1-PC5-Pad28)") (class "Default")
      (node (ref "U1") (pin "28") (pinfunction "PC5_28") (pintype "bidirectional"))
    )
  )
)
